# mbed_bob4.net
KiCad netlist of a schematic drawn in EAGLE
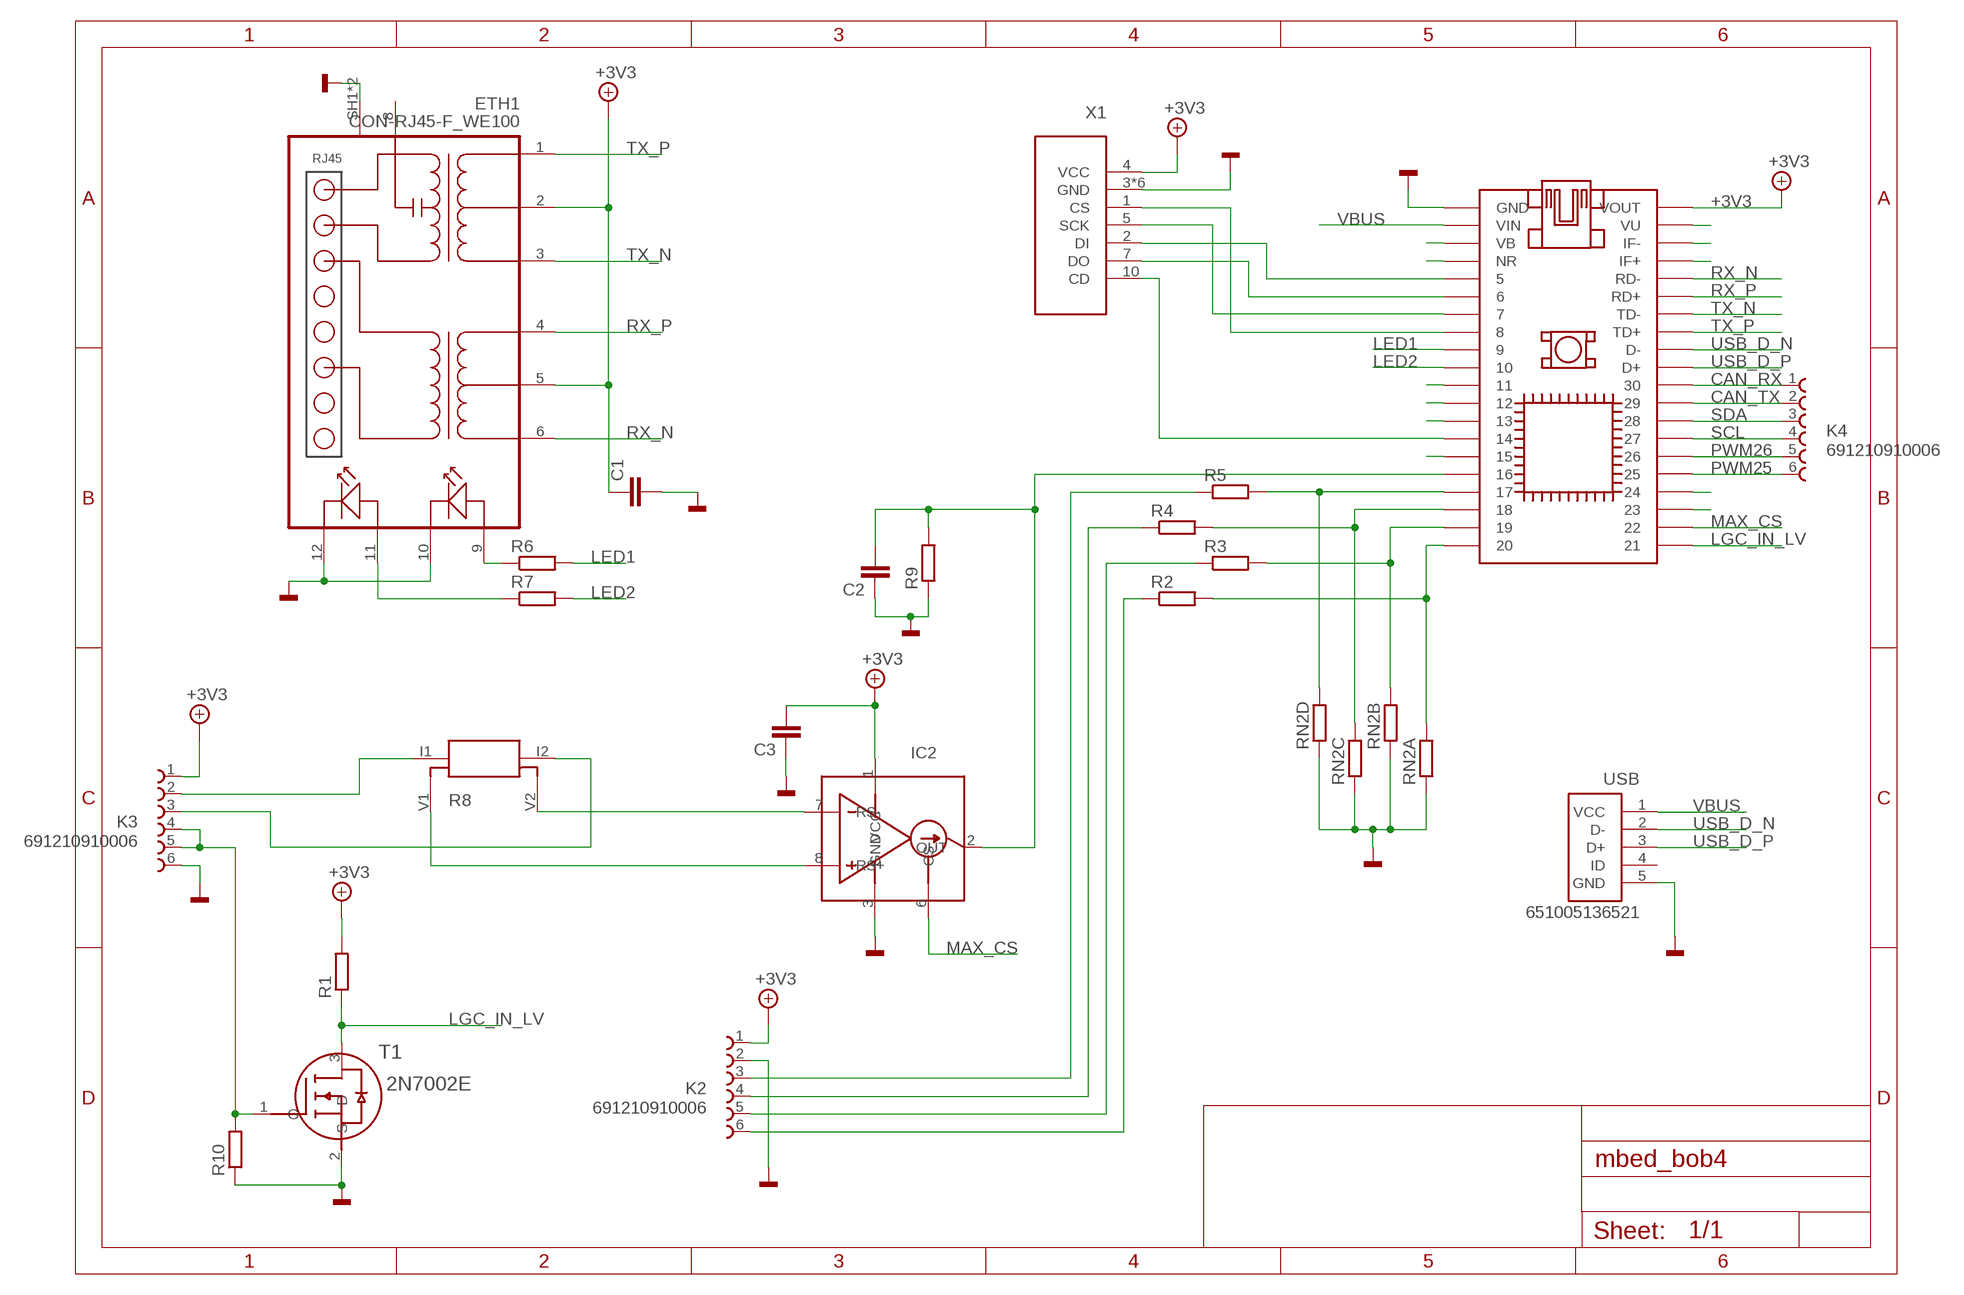
[diagram p0: schematic, sheet 1]

(export (version "E")
  (design (tool "Eeschema 10.0.6"))
  (components
    (comp (ref "C1")
      (value "C0805_RFLW")
      (footprint "eagle-import:0805_RFLW")
      (libsource (lib "eagle-import") (part "C0805_RFLW"))
    )
    (comp (ref "C2")
      (value "C0805_RFLW")
      (footprint "eagle-import:0805_RFLW")
      (libsource (lib "eagle-import") (part "C0805_RFLW"))
    )
    (comp (ref "C3")
      (value "C0805_RFLW")
      (footprint "eagle-import:0805_RFLW")
      (libsource (lib "eagle-import") (part "C0805_RFLW"))
    )
    (comp (ref "ETH1")
      (value "CON-RJ45-F_WE100")
      (footprint "eagle-import:74990111215A")
      (fields (field (name "MF") "Wuerth Elektronik") (field (name "MPN") "74990111215A"))
      (libsource (lib "eagle-import") (part "CON-RJ45-F_WE100"))
    )
    (comp (ref "IC1")
      (value "MBED-SOCKET")
      (footprint "eagle-import:MBED-SOCKET")
      (libsource (lib "eagle-import") (part "MBED-SOCKET"))
    )
    (comp (ref "IC2")
      (value "MAX9934")
      (footprint "eagle-import:UMAX8")
      (fields (field (name "MF") "Maxim"))
      (libsource (lib "eagle-import") (part "MAX9934"))
    )
    (comp (ref "K2")
      (value "691210910006")
      (footprint "eagle-import:691210910006")
      (libsource (lib "eagle-import") (part "691210910006"))
    )
    (comp (ref "K3")
      (value "691210910006")
      (footprint "eagle-import:691210910006")
      (libsource (lib "eagle-import") (part "691210910006"))
    )
    (comp (ref "K4")
      (value "691210910006")
      (footprint "eagle-import:691210910006")
      (libsource (lib "eagle-import") (part "691210910006"))
    )
    (comp (ref "R1")
      (value "R0805_RFLW")
      (footprint "eagle-import:0805_RFLW")
      (libsource (lib "eagle-import") (part "R0805_RFLW"))
    )
    (comp (ref "R2")
      (value "R0805_RFLW")
      (footprint "eagle-import:0805_RFLW")
      (libsource (lib "eagle-import") (part "R0805_RFLW"))
    )
    (comp (ref "R3")
      (value "R0805_RFLW")
      (footprint "eagle-import:0805_RFLW")
      (libsource (lib "eagle-import") (part "R0805_RFLW"))
    )
    (comp (ref "R4")
      (value "R0805_RFLW")
      (footprint "eagle-import:0805_RFLW")
      (libsource (lib "eagle-import") (part "R0805_RFLW"))
    )
    (comp (ref "R5")
      (value "R0805_RFLW")
      (footprint "eagle-import:0805_RFLW")
      (libsource (lib "eagle-import") (part "R0805_RFLW"))
    )
    (comp (ref "R6")
      (value "R0805_RFLW")
      (footprint "eagle-import:0805_RFLW")
      (libsource (lib "eagle-import") (part "R0805_RFLW"))
    )
    (comp (ref "R7")
      (value "R0805_RFLW")
      (footprint "eagle-import:0805_RFLW")
      (libsource (lib "eagle-import") (part "R0805_RFLW"))
    )
    (comp (ref "R8")
      (value "R_KELVIN")
      (footprint "eagle-import:R_KELVIN_1206")
      (fields (field (name "MF") "Ohmite"))
      (libsource (lib "eagle-import") (part "R_KELVIN"))
    )
    (comp (ref "R9")
      (value "R0805_RFLW")
      (footprint "eagle-import:0805_RFLW")
      (libsource (lib "eagle-import") (part "R0805_RFLW"))
    )
    (comp (ref "R10")
      (value "R0805_RFLW")
      (footprint "eagle-import:0805_RFLW")
      (libsource (lib "eagle-import") (part "R0805_RFLW"))
    )
    (comp (ref "RN2")
      (value "RESISTOR_ARRAY_4TC164")
      (footprint "eagle-import:RN_TC164")
      (fields (field (name "MF") "Yageo"))
      (libsource (lib "eagle-import") (part "RESISTOR_ARRAY_4TC164"))
    )
    (comp (ref "T1")
      (value "2N7002E")
      (footprint "eagle-import:SOT23-3L")
      (fields (field (name "MF") "NXP"))
      (libsource (lib "eagle-import") (part "2N7002E"))
    )
    (comp (ref "USB")
      (value "651005136521")
      (footprint "eagle-import:651005136521")
      (libsource (lib "eagle-import") (part "651005136521"))
    )
    (comp (ref "X1")
      (value "SDCARDSHORT")
      (footprint "eagle-import:SD_SHORT")
      (fields (field (name "MF") "Wuerth Elektronik") (field (name "MPN") "693063020911"))
      (libsource (lib "eagle-import") (part "SDCARDSHORT"))
    )
  )
  (nets
    (net (code "1") (name "+3V3") (class "Default")
      (node (ref "C1") (pin "P$3") (pinfunction "1_P$3") (pintype "passive"))
      (node (ref "C3") (pin "P$4") (pinfunction "2_P$4") (pintype "passive"))
      (node (ref "ETH1") (pin "2") (pinfunction "CTD_2") (pintype "bidirectional"))
      (node (ref "ETH1") (pin "5") (pinfunction "CRD_5") (pintype "bidirectional"))
      (node (ref "IC1") (pin "VOUT") (pinfunction "VOUT_VOUT") (pintype "bidirectional"))
      (node (ref "IC1") (pin "VOUTA") (pinfunction "VOUT_VOUTA") (pintype "bidirectional"))
      (node (ref "IC2") (pin "1") (pinfunction "VCC_1") (pintype "power_in"))
      (node (ref "K2") (pin "1") (pinfunction "1_1") (pintype "passive"))
      (node (ref "K3") (pin "1") (pinfunction "1_1") (pintype "passive"))
      (node (ref "R1") (pin "P$4") (pinfunction "2_P$4") (pintype "passive"))
      (node (ref "X1") (pin "4") (pinfunction "VCC_4") (pintype "power_in"))
    )
    (net (code "2") (name "/CAN_RX") (class "Default")
      (node (ref "IC1") (pin "30") (pinfunction "30_30") (pintype "bidirectional"))
      (node (ref "IC1") (pin "30A") (pinfunction "30_30A") (pintype "bidirectional"))
      (node (ref "K4") (pin "1") (pinfunction "1_1") (pintype "passive"))
    )
    (net (code "3") (name "/CAN_TX") (class "Default")
      (node (ref "IC1") (pin "29") (pinfunction "29_29") (pintype "bidirectional"))
      (node (ref "IC1") (pin "29A") (pinfunction "29_29A") (pintype "bidirectional"))
      (node (ref "K4") (pin "2") (pinfunction "2_2") (pintype "passive"))
    )
    (net (code "4") (name "/LED1") (class "Default")
      (node (ref "IC1") (pin "9") (pinfunction "9_9") (pintype "bidirectional"))
      (node (ref "IC1") (pin "9A") (pinfunction "9_9A") (pintype "bidirectional"))
      (node (ref "R6") (pin "P$4") (pinfunction "2_P$4") (pintype "passive"))
    )
    (net (code "5") (name "/LED2") (class "Default")
      (node (ref "IC1") (pin "10") (pinfunction "10_10") (pintype "bidirectional"))
      (node (ref "IC1") (pin "10A") (pinfunction "10_10A") (pintype "bidirectional"))
      (node (ref "R7") (pin "P$4") (pinfunction "2_P$4") (pintype "passive"))
    )
    (net (code "6") (name "/LGC_IN_LV") (class "Default")
      (node (ref "IC1") (pin "21") (pinfunction "21_21") (pintype "bidirectional"))
      (node (ref "IC1") (pin "21A") (pinfunction "21_21A") (pintype "bidirectional"))
      (node (ref "R1") (pin "P$3") (pinfunction "1_P$3") (pintype "passive"))
      (node (ref "T1") (pin "3") (pinfunction "D_3") (pintype "passive"))
    )
    (net (code "7") (name "/MAX_CS") (class "Default")
      (node (ref "IC1") (pin "22") (pinfunction "22_22") (pintype "bidirectional"))
      (node (ref "IC1") (pin "22A") (pinfunction "22_22A") (pintype "bidirectional"))
      (node (ref "IC2") (pin "6") (pinfunction "CS_6") (pintype "input"))
    )
    (net (code "8") (name "/PWM25") (class "Default")
      (node (ref "IC1") (pin "25") (pinfunction "25_25") (pintype "bidirectional"))
      (node (ref "IC1") (pin "25A") (pinfunction "25_25A") (pintype "bidirectional"))
      (node (ref "K4") (pin "6") (pinfunction "6_6") (pintype "passive"))
    )
    (net (code "9") (name "/PWM26") (class "Default")
      (node (ref "IC1") (pin "26") (pinfunction "26_26") (pintype "bidirectional"))
      (node (ref "IC1") (pin "26A") (pinfunction "26_26A") (pintype "bidirectional"))
      (node (ref "K4") (pin "5") (pinfunction "5_5") (pintype "passive"))
    )
    (net (code "10") (name "/RX_N") (class "Default")
      (node (ref "ETH1") (pin "6") (pinfunction "RD-_6") (pintype "bidirectional"))
      (node (ref "IC1") (pin "RD-") (pinfunction "RD-_RD-") (pintype "bidirectional"))
      (node (ref "IC1") (pin "RD-A") (pinfunction "RD-_RD-A") (pintype "bidirectional"))
    )
    (net (code "11") (name "/RX_P") (class "Default")
      (node (ref "ETH1") (pin "4") (pinfunction "RD+_4") (pintype "bidirectional"))
      (node (ref "IC1") (pin "RD+") (pinfunction "RD+_RD+") (pintype "bidirectional"))
      (node (ref "IC1") (pin "RD+A") (pinfunction "RD+_RD+A") (pintype "bidirectional"))
    )
    (net (code "12") (name "/SCL") (class "Default")
      (node (ref "IC1") (pin "27") (pinfunction "27_27") (pintype "bidirectional"))
      (node (ref "IC1") (pin "27A") (pinfunction "27_27A") (pintype "bidirectional"))
      (node (ref "K4") (pin "4") (pinfunction "4_4") (pintype "passive"))
    )
    (net (code "13") (name "/SDA") (class "Default")
      (node (ref "IC1") (pin "28") (pinfunction "28_28") (pintype "bidirectional"))
      (node (ref "IC1") (pin "28A") (pinfunction "28_28A") (pintype "bidirectional"))
      (node (ref "K4") (pin "3") (pinfunction "3_3") (pintype "passive"))
    )
    (net (code "14") (name "/TX_N") (class "Default")
      (node (ref "ETH1") (pin "3") (pinfunction "TD-_3") (pintype "bidirectional"))
      (node (ref "IC1") (pin "TD-") (pinfunction "TD-_TD-") (pintype "bidirectional"))
      (node (ref "IC1") (pin "TD-A") (pinfunction "TD-_TD-A") (pintype "bidirectional"))
    )
    (net (code "15") (name "/TX_P") (class "Default")
      (node (ref "ETH1") (pin "1") (pinfunction "TD+_1") (pintype "bidirectional"))
      (node (ref "IC1") (pin "TD+") (pinfunction "TD+_TD+") (pintype "bidirectional"))
      (node (ref "IC1") (pin "TD+A") (pinfunction "TD+_TD+A") (pintype "bidirectional"))
    )
    (net (code "16") (name "/USB_D_N") (class "Default")
      (node (ref "IC1") (pin "D-") (pinfunction "D-_D-") (pintype "bidirectional"))
      (node (ref "IC1") (pin "D-A") (pinfunction "D-_D-A") (pintype "bidirectional"))
      (node (ref "USB") (pin "2") (pinfunction "D-_2") (pintype "passive"))
    )
    (net (code "17") (name "/USB_D_P") (class "Default")
      (node (ref "IC1") (pin "D+") (pinfunction "D+_D+") (pintype "bidirectional"))
      (node (ref "IC1") (pin "D+A") (pinfunction "D+_D+A") (pintype "bidirectional"))
      (node (ref "USB") (pin "3") (pinfunction "D+_3") (pintype "passive"))
    )
    (net (code "18") (name "/VBUS") (class "Default")
      (node (ref "IC1") (pin "VIN") (pinfunction "VIN_VIN") (pintype "bidirectional"))
      (node (ref "IC1") (pin "VINA") (pinfunction "VIN_VINA") (pintype "bidirectional"))
      (node (ref "USB") (pin "1") (pinfunction "VCC_1") (pintype "passive"))
    )
    (net (code "19") (name "GND") (class "Default")
      (node (ref "C1") (pin "P$4") (pinfunction "2_P$4") (pintype "passive"))
      (node (ref "C2") (pin "P$3") (pinfunction "1_P$3") (pintype "passive"))
      (node (ref "C3") (pin "P$3") (pinfunction "1_P$3") (pintype "passive"))
      (node (ref "ETH1") (pin "10") (pinfunction "YELLOW_CATHODE_10") (pintype "bidirectional"))
      (node (ref "ETH1") (pin "12") (pinfunction "GREEN_CATHODE_12") (pintype "bidirectional"))
      (node (ref "ETH1") (pin "SH1") (pinfunction "SHIELD_SH1") (pintype "bidirectional"))
      (node (ref "ETH1") (pin "SH2") (pinfunction "SHIELD_SH2") (pintype "bidirectional"))
      (node (ref "IC1") (pin "GND") (pinfunction "GND_GND") (pintype "bidirectional"))
      (node (ref "IC1") (pin "GNDA") (pinfunction "GND_GNDA") (pintype "bidirectional"))
      (node (ref "IC2") (pin "3") (pinfunction "GND_3") (pintype "power_in"))
      (node (ref "K2") (pin "2") (pinfunction "2_2") (pintype "passive"))
      (node (ref "K3") (pin "6") (pinfunction "6_6") (pintype "passive"))
      (node (ref "R10") (pin "P$3") (pinfunction "1_P$3") (pintype "passive"))
      (node (ref "R9") (pin "P$3") (pinfunction "1_P$3") (pintype "passive"))
      (node (ref "RN2") (pin "1") (pinfunction "1_1") (pintype "passive"))
      (node (ref "RN2") (pin "2") (pinfunction "1_2") (pintype "passive"))
      (node (ref "RN2") (pin "3") (pinfunction "1_3") (pintype "passive"))
      (node (ref "RN2") (pin "4") (pinfunction "1_4") (pintype "passive"))
      (node (ref "T1") (pin "2") (pinfunction "S_2") (pintype "passive"))
      (node (ref "USB") (pin "5") (pinfunction "GND_5") (pintype "passive"))
      (node (ref "X1") (pin "3") (pinfunction "GND_3") (pintype "power_in"))
      (node (ref "X1") (pin "6") (pinfunction "GND_6") (pintype "power_in"))
      (node (ref "X1") (pin "GND@1") (pinfunction "GND_GND@1") (pintype "power_in"))
      (node (ref "X1") (pin "GND@2") (pinfunction "GND_GND@2") (pintype "power_in"))
      (node (ref "X1") (pin "GND@3") (pinfunction "GND_GND@3") (pintype "power_in"))
      (node (ref "X1") (pin "GND@4") (pinfunction "GND_GND@4") (pintype "power_in"))
    )
    (net (code "20") (name "Net-(C2-2)") (class "Default")
      (node (ref "C2") (pin "P$4") (pinfunction "2_P$4") (pintype "passive"))
      (node (ref "IC1") (pin "16") (pinfunction "16_16") (pintype "bidirectional"))
      (node (ref "IC1") (pin "16A") (pinfunction "16_16A") (pintype "bidirectional"))
      (node (ref "IC2") (pin "2") (pinfunction "OUT_2") (pintype "output"))
      (node (ref "R9") (pin "P$4") (pinfunction "2_P$4") (pintype "passive"))
    )
    (net (code "21") (name "Net-(ETH1-GREEN_ANODE)") (class "Default")
      (node (ref "ETH1") (pin "11") (pinfunction "GREEN_ANODE_11") (pintype "bidirectional"))
      (node (ref "R7") (pin "P$3") (pinfunction "1_P$3") (pintype "passive"))
    )
    (net (code "22") (name "Net-(ETH1-YELLOW_ANODE)") (class "Default")
      (node (ref "ETH1") (pin "9") (pinfunction "YELLOW_ANODE_9") (pintype "bidirectional"))
      (node (ref "R6") (pin "P$3") (pinfunction "1_P$3") (pintype "passive"))
    )
    (net (code "23") (name "Net-(IC1-11-Pad11A)") (class "Default")
      (node (ref "IC1") (pin "11") (pinfunction "11_11") (pintype "bidirectional"))
      (node (ref "IC1") (pin "11A") (pinfunction "11_11A") (pintype "bidirectional"))
    )
    (net (code "24") (name "Net-(IC1-12-Pad12A)") (class "Default")
      (node (ref "IC1") (pin "12") (pinfunction "12_12") (pintype "bidirectional"))
      (node (ref "IC1") (pin "12A") (pinfunction "12_12A") (pintype "bidirectional"))
    )
    (net (code "25") (name "Net-(IC1-13-Pad13A)") (class "Default")
      (node (ref "IC1") (pin "13") (pinfunction "13_13") (pintype "bidirectional"))
      (node (ref "IC1") (pin "13A") (pinfunction "13_13A") (pintype "bidirectional"))
    )
    (net (code "26") (name "Net-(IC1-15-Pad15A)") (class "Default")
      (node (ref "IC1") (pin "15") (pinfunction "15_15") (pintype "bidirectional"))
      (node (ref "IC1") (pin "15A") (pinfunction "15_15A") (pintype "bidirectional"))
    )
    (net (code "27") (name "Net-(IC1-23-Pad23A)") (class "Default")
      (node (ref "IC1") (pin "23") (pinfunction "23_23") (pintype "bidirectional"))
      (node (ref "IC1") (pin "23A") (pinfunction "23_23A") (pintype "bidirectional"))
    )
    (net (code "28") (name "Net-(IC1-24-Pad24A)") (class "Default")
      (node (ref "IC1") (pin "24") (pinfunction "24_24") (pintype "bidirectional"))
      (node (ref "IC1") (pin "24A") (pinfunction "24_24A") (pintype "bidirectional"))
    )
    (net (code "29") (name "Net-(IC1-IF+-PadIF+A)") (class "Default")
      (node (ref "IC1") (pin "IF+") (pinfunction "IF+_IF+") (pintype "bidirectional"))
      (node (ref "IC1") (pin "IF+A") (pinfunction "IF+_IF+A") (pintype "bidirectional"))
    )
    (net (code "30") (name "Net-(IC1-IF--PadIF-A)") (class "Default")
      (node (ref "IC1") (pin "IF-") (pinfunction "IF-_IF-") (pintype "bidirectional"))
      (node (ref "IC1") (pin "IF-A") (pinfunction "IF-_IF-A") (pintype "bidirectional"))
    )
    (net (code "31") (name "Net-(IC1-NR-PadNRA)") (class "Default")
      (node (ref "IC1") (pin "NR") (pinfunction "NR_NR") (pintype "bidirectional"))
      (node (ref "IC1") (pin "NRA") (pinfunction "NR_NRA") (pintype "bidirectional"))
    )
    (net (code "32") (name "Net-(IC1-PadVB)") (class "Default")
      (node (ref "IC1") (pin "VB") (pinfunction "VB_VB") (pintype "bidirectional"))
      (node (ref "IC1") (pin "VBA") (pinfunction "VB_VBA") (pintype "bidirectional"))
    )
    (net (code "33") (name "Net-(IC1-PadVU)") (class "Default")
      (node (ref "IC1") (pin "VU") (pinfunction "VU_VU") (pintype "bidirectional"))
      (node (ref "IC1") (pin "VUA") (pinfunction "VU_VUA") (pintype "bidirectional"))
    )
    (net (code "34") (name "Net-(IC2-RS+)") (class "Default")
      (node (ref "IC2") (pin "8") (pinfunction "RS+_8") (pintype "input"))
      (node (ref "R8") (pin "V1") (pinfunction "V1_V1") (pintype "passive"))
    )
    (net (code "35") (name "Net-(IC2-RS-)") (class "Default")
      (node (ref "IC2") (pin "7") (pinfunction "RS-_7") (pintype "input"))
      (node (ref "R8") (pin "V2") (pinfunction "V2_V2") (pintype "passive"))
    )
    (net (code "36") (name "Net-(K3-Pad2)") (class "Default")
      (node (ref "K3") (pin "2") (pinfunction "2_2") (pintype "passive"))
      (node (ref "R8") (pin "I1") (pinfunction "I1_I1") (pintype "passive"))
    )
    (net (code "37") (name "Net-(K3-Pad3)") (class "Default")
      (node (ref "K3") (pin "3") (pinfunction "3_3") (pintype "passive"))
      (node (ref "R8") (pin "I2") (pinfunction "I2_I2") (pintype "passive"))
    )
    (net (code "38") (name "Net-(R2-1)") (class "Default")
      (node (ref "K2") (pin "6") (pinfunction "6_6") (pintype "passive"))
      (node (ref "R2") (pin "P$3") (pinfunction "1_P$3") (pintype "passive"))
    )
    (net (code "39") (name "Net-(R2-2)") (class "Default")
      (node (ref "IC1") (pin "20") (pinfunction "20_20") (pintype "bidirectional"))
      (node (ref "IC1") (pin "20A") (pinfunction "20_20A") (pintype "bidirectional"))
      (node (ref "R2") (pin "P$4") (pinfunction "2_P$4") (pintype "passive"))
      (node (ref "RN2") (pin "8") (pinfunction "2_8") (pintype "passive"))
    )
    (net (code "40") (name "Net-(R3-1)") (class "Default")
      (node (ref "K2") (pin "5") (pinfunction "5_5") (pintype "passive"))
      (node (ref "R3") (pin "P$3") (pinfunction "1_P$3") (pintype "passive"))
    )
    (net (code "41") (name "Net-(R3-2)") (class "Default")
      (node (ref "IC1") (pin "19") (pinfunction "19_19") (pintype "bidirectional"))
      (node (ref "IC1") (pin "19A") (pinfunction "19_19A") (pintype "bidirectional"))
      (node (ref "R3") (pin "P$4") (pinfunction "2_P$4") (pintype "passive"))
      (node (ref "RN2") (pin "7") (pinfunction "2_7") (pintype "passive"))
    )
    (net (code "42") (name "Net-(R4-1)") (class "Default")
      (node (ref "K2") (pin "4") (pinfunction "4_4") (pintype "passive"))
      (node (ref "R4") (pin "P$3") (pinfunction "1_P$3") (pintype "passive"))
    )
    (net (code "43") (name "Net-(R4-2)") (class "Default")
      (node (ref "IC1") (pin "18") (pinfunction "18_18") (pintype "bidirectional"))
      (node (ref "IC1") (pin "18A") (pinfunction "18_18A") (pintype "bidirectional"))
      (node (ref "R4") (pin "P$4") (pinfunction "2_P$4") (pintype "passive"))
      (node (ref "RN2") (pin "6") (pinfunction "2_6") (pintype "passive"))
    )
    (net (code "44") (name "Net-(R5-1)") (class "Default")
      (node (ref "K2") (pin "3") (pinfunction "3_3") (pintype "passive"))
      (node (ref "R5") (pin "P$3") (pinfunction "1_P$3") (pintype "passive"))
    )
    (net (code "45") (name "Net-(R5-2)") (class "Default")
      (node (ref "IC1") (pin "17") (pinfunction "17_17") (pintype "bidirectional"))
      (node (ref "IC1") (pin "17A") (pinfunction "17_17A") (pintype "bidirectional"))
      (node (ref "R5") (pin "P$4") (pinfunction "2_P$4") (pintype "passive"))
      (node (ref "RN2") (pin "5") (pinfunction "2_5") (pintype "passive"))
    )
    (net (code "46") (name "Net-(R10-2)") (class "Default")
      (node (ref "K3") (pin "4") (pinfunction "4_4") (pintype "passive"))
      (node (ref "K3") (pin "5") (pinfunction "5_5") (pintype "passive"))
      (node (ref "R10") (pin "P$4") (pinfunction "2_P$4") (pintype "passive"))
      (node (ref "T1") (pin "1") (pinfunction "G_1") (pintype "passive"))
    )
    (net (code "47") (name "Net-(X1-CD)") (class "Default")
      (node (ref "IC1") (pin "14") (pinfunction "14_14") (pintype "bidirectional"))
      (node (ref "IC1") (pin "14A") (pinfunction "14_14A") (pintype "bidirectional"))
      (node (ref "X1") (pin "10") (pinfunction "CD_10") (pintype "output"))
    )
    (net (code "48") (name "Net-(X1-CS)") (class "Default")
      (node (ref "IC1") (pin "8") (pinfunction "8_8") (pintype "bidirectional"))
      (node (ref "IC1") (pin "8A") (pinfunction "8_8A") (pintype "bidirectional"))
      (node (ref "X1") (pin "1") (pinfunction "CS_1") (pintype "input"))
    )
    (net (code "49") (name "Net-(X1-DI)") (class "Default")
      (node (ref "IC1") (pin "5") (pinfunction "5_5") (pintype "bidirectional"))
      (node (ref "IC1") (pin "5A") (pinfunction "5_5A") (pintype "bidirectional"))
      (node (ref "X1") (pin "2") (pinfunction "DI_2") (pintype "input"))
    )
    (net (code "50") (name "Net-(X1-DO)") (class "Default")
      (node (ref "IC1") (pin "6") (pinfunction "6_6") (pintype "bidirectional"))
      (node (ref "IC1") (pin "6A") (pinfunction "6_6A") (pintype "bidirectional"))
      (node (ref "X1") (pin "7") (pinfunction "DO_7") (pintype "output"))
    )
    (net (code "51") (name "Net-(X1-SCK)") (class "Default")
      (node (ref "IC1") (pin "7") (pinfunction "7_7") (pintype "bidirectional"))
      (node (ref "IC1") (pin "7A") (pinfunction "7_7A") (pintype "bidirectional"))
      (node (ref "X1") (pin "5") (pinfunction "SCK_5") (pintype "input"))
    )
    (net (code "52") (name "unconnected-(ETH1-EXT_TAP-Pad8)") (class "Default")
      (node (ref "ETH1") (pin "8") (pinfunction "EXT_TAP_8") (pintype "bidirectional"))
    )
    (net (code "53") (name "unconnected-(USB-ID-Pad4)") (class "Default")
      (node (ref "USB") (pin "4") (pinfunction "ID_4") (pintype "passive"))
    )
  )
)
